# Ethernet-PoE-Sheet.net
KiCad netlist of a schematic drawn in Altium Designer
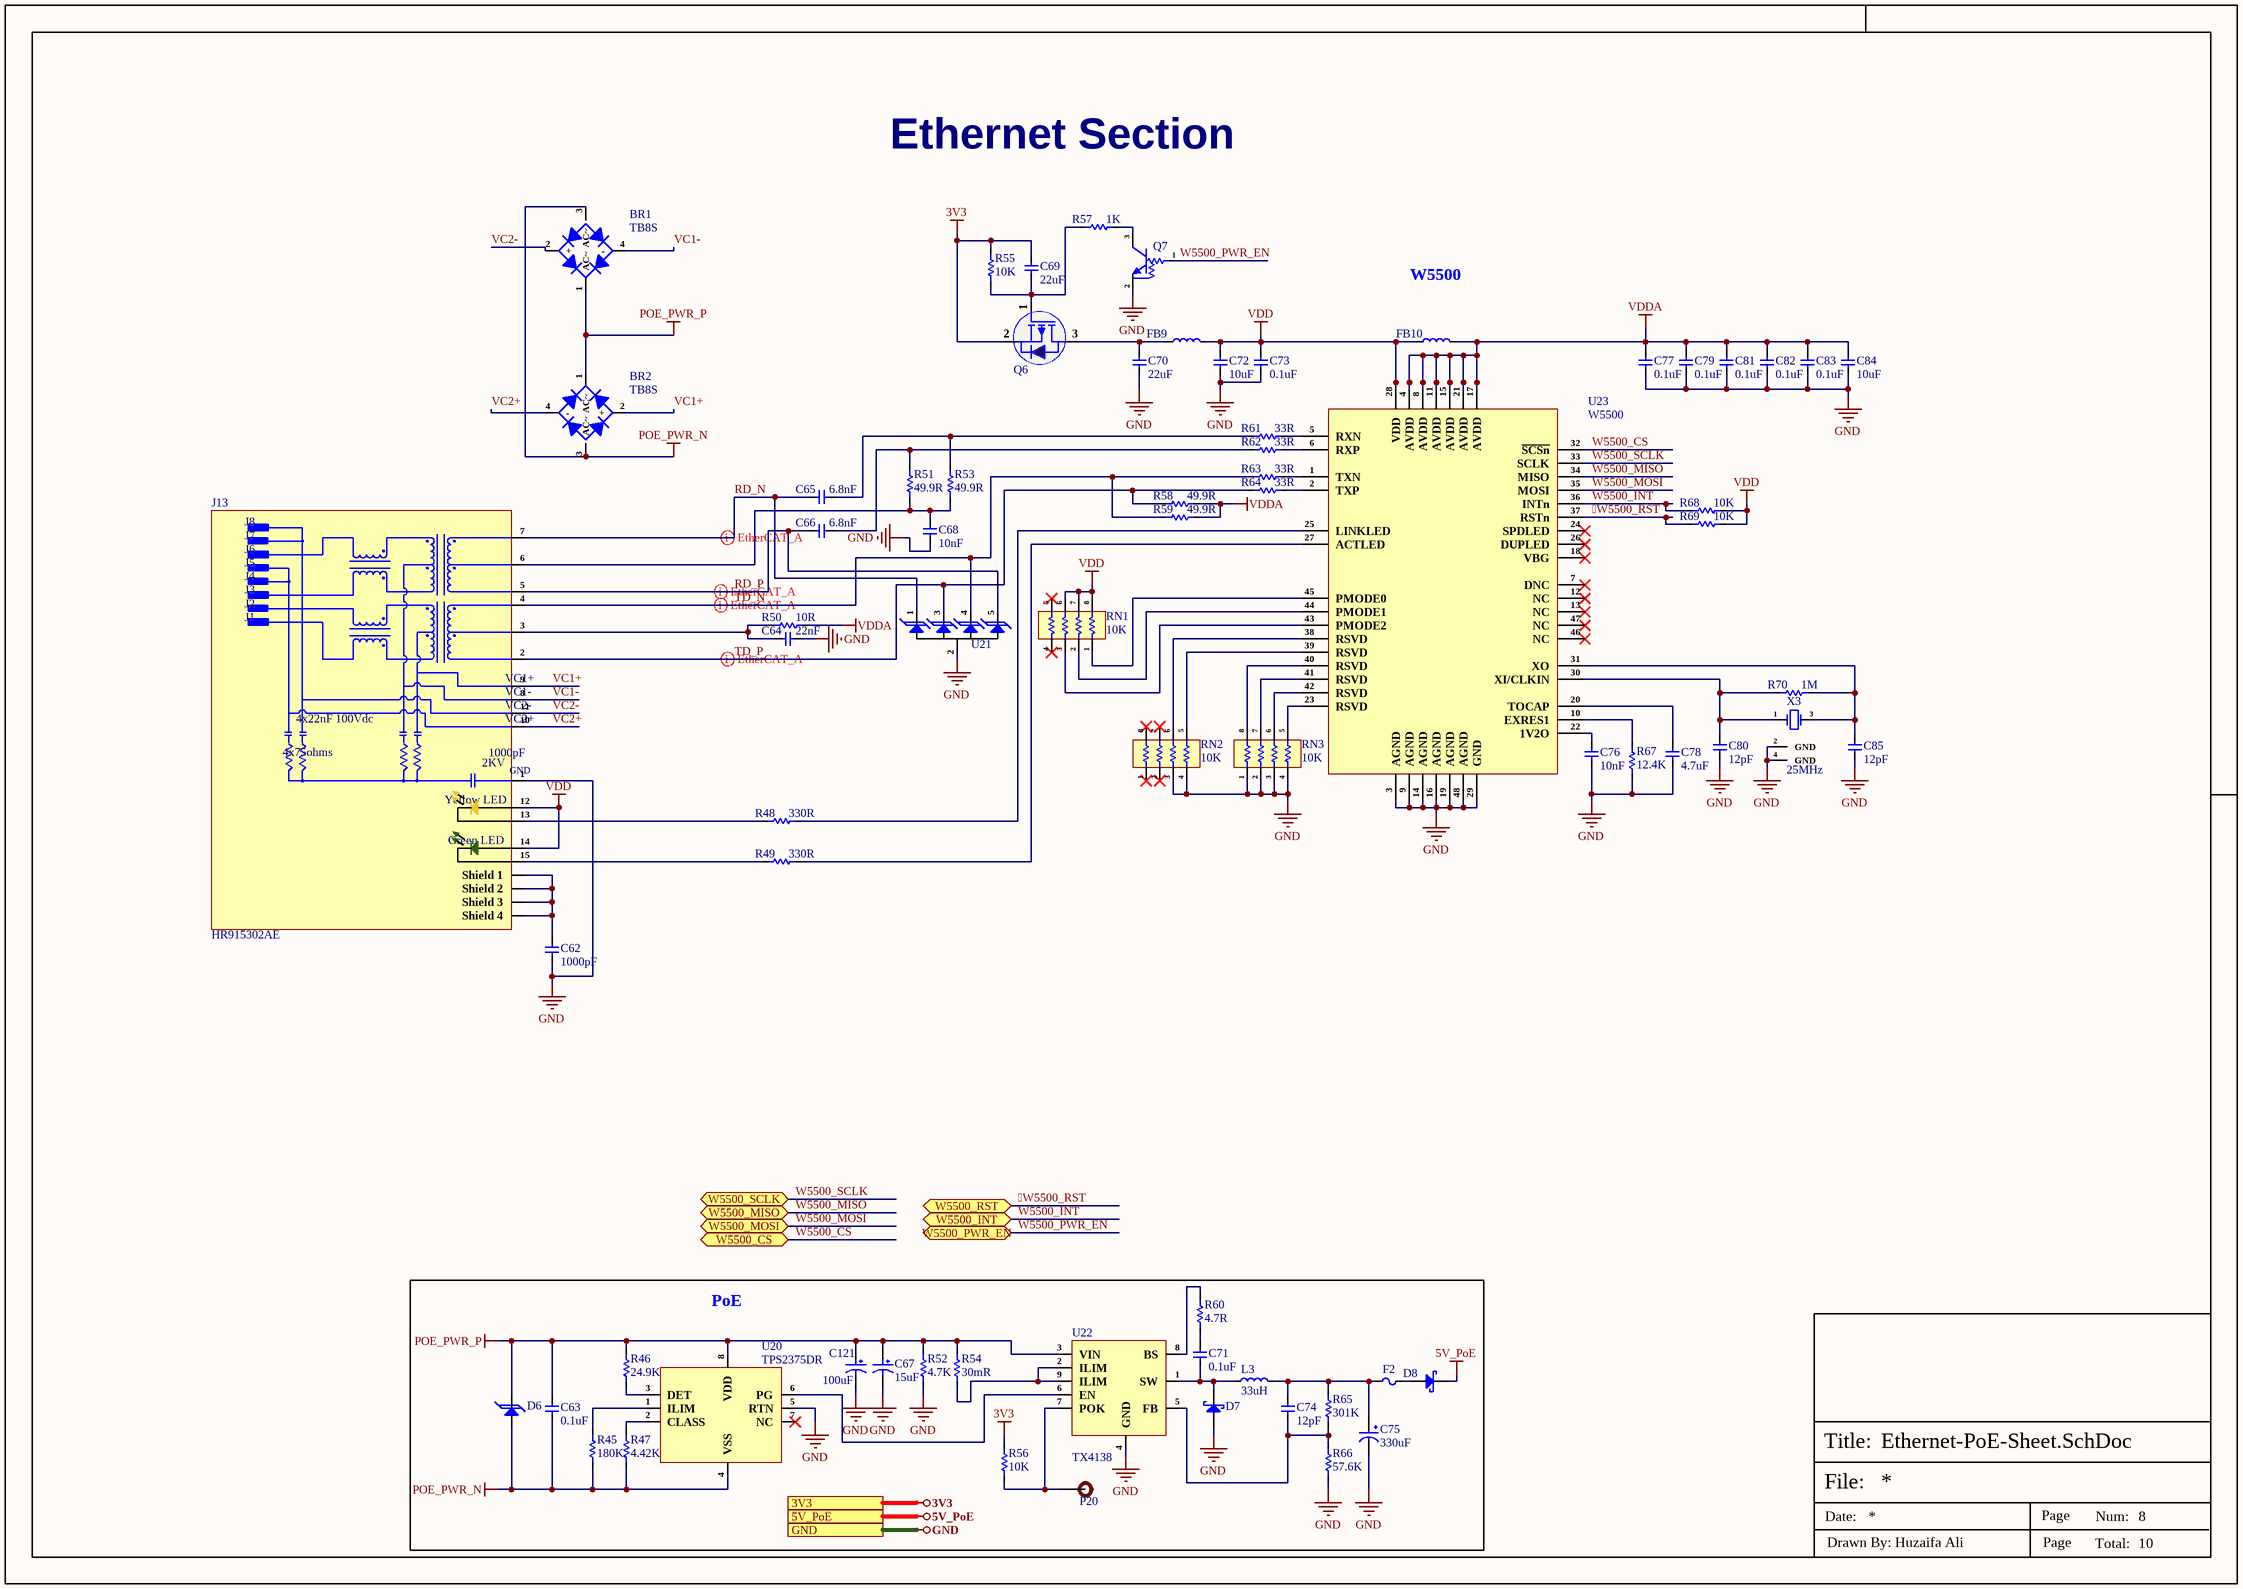
[diagram p0: Ethernet-PoE-Sheet.SchDoc]

(export (version "E")
  (design (tool "Eeschema 10.0.6"))
  (components
    (comp (ref "BR1")
      (value "TB8S")
      (footprint "TB8S")
      (description "30A 950mV@1A 1A 800V TBS Bridge Rectifiers ROHS")
      (fields (field (name "MANUFACTURER") "MDD") (field (name "LCSC PART NUMBER") "C65030"))
      (libsource (lib "eSpark Libraries") (part "TB8S"))
    )
    (comp (ref "BR2")
      (value "TB8S")
      (footprint "TB8S")
      (description "30A 950mV@1A 1A 800V TBS Bridge Rectifiers ROHS")
      (fields (field (name "MANUFACTURER") "MDD") (field (name "LCSC PART NUMBER") "C65030"))
      (libsource (lib "eSpark Libraries") (part "TB8S"))
    )
    (comp (ref "C62")
      (value "1000pF")
      (footprint "Cap-1206")
      (description "CAP CER 1000PF 2KV X7R 1206")
      (fields
        (field (name "MANUFACTURER") "Yageo")
        (field (name "MANUFACTURER PART NUMBER") "CC1206KKX7RDBB102")
      )
      (libsource (lib "eSpark_centralized_Library(2022)") (part "CC1206KKX7RDBB102"))
    )
    (comp (ref "C63")
      (value "0.1uF")
      (footprint "Cap-0603")
      (description "CAP CER 0.1UF 100V X7R 0603")
      (fields
        (field (name "MANUFACTURER") "Yageo")
        (field (name "MANUFACTURER PART NUMBER") "CC0603KRX7R0BB104")
      )
      (libsource (lib "eSpark_centralized_Library(2022)") (part "CC0603KRX7R0BB104"))
    )
    (comp (ref "C64")
      (value "22nF")
      (footprint "Cap-0603")
      (description "CAP CER 0.022UF 50V X7R 0603")
      (fields
        (field (name "MANUFACTURER") "Yageo")
        (field (name "MANUFACTURER PART NUMBER") "CC0603KRX7R9BB223")
      )
      (libsource (lib "eSpark_centralized_Library(2022)") (part "CC0603KRX7R9BB223"))
    )
    (comp (ref "C65")
      (value "6.8nF")
      (footprint "Cap-0603")
      (description "50V 6.8nF X7R ±10% 0603")
      (fields (field (name "MANUFACTURER") "FH") (field (name "MANUFACTURER PART NUMBER") "0603B682K500NT"))
      (libsource (lib "eSpark_centralized_Library(2022)") (part "0603B682K500NT"))
    )
    (comp (ref "C66")
      (value "6.8nF")
      (footprint "Cap-0603")
      (description "50V 6.8nF X7R ±10% 0603")
      (fields (field (name "MANUFACTURER") "FH") (field (name "MANUFACTURER PART NUMBER") "0603B682K500NT"))
      (libsource (lib "eSpark_centralized_Library(2022)") (part "0603B682K500NT"))
    )
    (comp (ref "C67")
      (value "15uF")
      (footprint "VMMC0571J150MV")
      (description "15uF 63V ±20% SMD,D6.3xL5.7mm Aluminum Electrolytic Capacitors - SMD ROHS")
      (fields (field (name "MANUFACTURER") "Ymin") (field (name "MANUFACTURER PART NUMBER") "VMMC0571J150MV"))
      (libsource (lib "eSpark_centralized_Library(2022)") (part "VMMC0571J150MV"))
    )
    (comp (ref "C68")
      (value "10nF")
      (footprint "Cap-0603")
      (description "CAP CER 10000PF 50V C0G/NPO 0603")
      (fields
        (field (name "MANUFACTURER") "Yageo")
        (field (name "MANUFACTURER PART NUMBER") "CC0603JRNPO9BN103")
      )
      (libsource (lib "eSpark_centralized_Library(2022)") (part "CC0603JRNPO9BN103"))
    )
    (comp (ref "C69")
      (value "22uF")
      (footprint "Cap-0805")
      (description "CAP CER 22UF 25V X5R 0805")
      (fields
        (field (name "MANUFACTURER") "Yageo")
        (field (name "MANUFACTURER PART NUMBER") "CC0805MKX5R8BB226")
      )
      (libsource (lib "eSpark_centralized_Library(2022)") (part "CC0805MKX5R8BB226"))
    )
    (comp (ref "C70")
      (value "22uF")
      (footprint "Cap-0805")
      (description "CAP CER 22UF 25V X5R 0805")
      (fields
        (field (name "MANUFACTURER") "Yageo")
        (field (name "MANUFACTURER PART NUMBER") "CC0805MKX5R8BB226")
      )
      (libsource (lib "eSpark_centralized_Library(2022)") (part "CC0805MKX5R8BB226"))
    )
    (comp (ref "C71")
      (value "0.1uF")
      (footprint "Cap-0603")
      (description "CAP CER 0.1UF 100V X7R 0603")
      (fields
        (field (name "MANUFACTURER") "Yageo")
        (field (name "MANUFACTURER PART NUMBER") "CC0603KRX7R0BB104")
      )
      (libsource (lib "eSpark_centralized_Library(2022)") (part "CC0603KRX7R0BB104"))
    )
    (comp (ref "C72")
      (value "10uF")
      (footprint "Cap-0603")
      (description "CAP CER 10UF 16V X5R 0603")
      (fields
        (field (name "MANUFACTURER") "Yageo")
        (field (name "MANUFACTURER PART NUMBER") "CC0603KRX5R7BB106")
      )
      (libsource (lib "eSpark_centralized_Library(2022)") (part "CC0603KRX5R7BB106"))
    )
    (comp (ref "C73")
      (value "0.1uF")
      (footprint "Cap-0402")
      (description "CAP CER 0.1UF 50V X5R 0402")
      (fields
        (field (name "MANUFACTURER") "TDK")
        (field (name "MANUFACTURER PART NUMBER") "C1005X5R1H104K050BB")
      )
      (libsource (lib "eSpark_centralized_Library(2022)") (part "C1005X5R1H104K050BB"))
    )
    (comp (ref "C74")
      (value "12pF")
      (footprint "Cap-0603")
      (description "CAP CER 12PF 50V C0G/NPO 0603")
      (fields
        (field (name "MANUFACTURER") "Yageo")
        (field (name "MANUFACTURER PART NUMBER") "CC0603J*NPO9B*120")
      )
      (libsource (lib "eSpark_centralized_Library(2022)") (part "CC0603JRNPO9BN120"))
    )
    (comp (ref "C75")
      (value "330uF")
      (footprint "Case-E")
      (description "CAP TANT 330UF 20% 16V 2917")
      (fields
        (field (name "MANUFACTURER") "Kyocera AVX")
        (field (name "MANUFACTURER PART NUMBER") "TAJE337M016RNJ")
      )
      (libsource (lib "eSpark_centralized_Library(2022)") (part "TAJE337M016RNJ"))
    )
    (comp (ref "C76")
      (value "10nF")
      (footprint "Cap-0603")
      (description "CAP CER 10000PF 50V C0G/NPO 0603")
      (fields
        (field (name "MANUFACTURER") "Yageo")
        (field (name "MANUFACTURER PART NUMBER") "CC0603JRNPO9BN103")
      )
      (libsource (lib "eSpark_centralized_Library(2022)") (part "CC0603JRNPO9BN103"))
    )
    (comp (ref "C77")
      (value "0.1uF")
      (footprint "Cap-0402")
      (description "CAP CER 0.1UF 50V X5R 0402")
      (fields
        (field (name "MANUFACTURER") "TDK")
        (field (name "MANUFACTURER PART NUMBER") "C1005X5R1H104K050BB")
      )
      (libsource (lib "eSpark_centralized_Library(2022)") (part "C1005X5R1H104K050BB"))
    )
    (comp (ref "C78")
      (value "4.7uF")
      (footprint "Cap-0603")
      (description "CAP CER 4.7UF 10V X5R 0603")
      (fields
        (field (name "MANUFACTURER") "Yageo")
        (field (name "MANUFACTURER PART NUMBER") "CC0603KRX5R6BB475")
      )
      (libsource (lib "eSpark_centralized_Library(2022)") (part "CC0603KRX5R6BB475"))
    )
    (comp (ref "C79")
      (value "0.1uF")
      (footprint "Cap-0402")
      (description "CAP CER 0.1UF 50V X5R 0402")
      (fields
        (field (name "MANUFACTURER") "TDK")
        (field (name "MANUFACTURER PART NUMBER") "C1005X5R1H104K050BB")
      )
      (libsource (lib "eSpark_centralized_Library(2022)") (part "C1005X5R1H104K050BB"))
    )
    (comp (ref "C80")
      (value "12pF")
      (footprint "Cap-0603")
      (description "CAP CER 12PF 50V C0G/NPO 0603")
      (fields
        (field (name "MANUFACTURER") "Yageo")
        (field (name "MANUFACTURER PART NUMBER") "CC0603J*NPO9B*120")
      )
      (libsource (lib "eSpark_centralized_Library(2022)") (part "CC0603JRNPO9BN120"))
    )
    (comp (ref "C81")
      (value "0.1uF")
      (footprint "Cap-0402")
      (description "CAP CER 0.1UF 50V X5R 0402")
      (fields
        (field (name "MANUFACTURER") "TDK")
        (field (name "MANUFACTURER PART NUMBER") "C1005X5R1H104K050BB")
      )
      (libsource (lib "eSpark_centralized_Library(2022)") (part "C1005X5R1H104K050BB"))
    )
    (comp (ref "C82")
      (value "0.1uF")
      (footprint "Cap-0402")
      (description "CAP CER 0.1UF 50V X5R 0402")
      (fields
        (field (name "MANUFACTURER") "TDK")
        (field (name "MANUFACTURER PART NUMBER") "C1005X5R1H104K050BB")
      )
      (libsource (lib "eSpark_centralized_Library(2022)") (part "C1005X5R1H104K050BB"))
    )
    (comp (ref "C83")
      (value "0.1uF")
      (footprint "Cap-0402")
      (description "CAP CER 0.1UF 50V X5R 0402")
      (fields
        (field (name "MANUFACTURER") "TDK")
        (field (name "MANUFACTURER PART NUMBER") "C1005X5R1H104K050BB")
      )
      (libsource (lib "eSpark_centralized_Library(2022)") (part "C1005X5R1H104K050BB"))
    )
    (comp (ref "C84")
      (value "10uF")
      (footprint "Cap-0603")
      (description "CAP CER 10UF 16V X5R 0603")
      (fields
        (field (name "MANUFACTURER") "Yageo")
        (field (name "MANUFACTURER PART NUMBER") "CC0603KRX5R7BB106")
      )
      (libsource (lib "eSpark_centralized_Library(2022)") (part "CC0603KRX5R7BB106"))
    )
    (comp (ref "C85")
      (value "12pF")
      (footprint "Cap-0603")
      (description "CAP CER 12PF 50V C0G/NPO 0603")
      (fields
        (field (name "MANUFACTURER") "Yageo")
        (field (name "MANUFACTURER PART NUMBER") "CC0603J*NPO9B*120")
      )
      (libsource (lib "eSpark_centralized_Library(2022)") (part "CC0603JRNPO9BN120"))
    )
    (comp (ref "C121")
      (value "100uF")
      (footprint "VKMD1451K101MV")
      (description "100uF 80V 735mA@100kHz ±20% SMD,D8xL14.5mm Aluminum Electrolytic Capacitors - SMD ROHS")
      (fields (field (name "MANUFACTURER") "Ymin") (field (name "MANUFACTURER PART NUMBER") "VKMD1451K101MV"))
      (libsource (lib "eSpark Libraries") (part "VKMD1451K101MV"))
    )
    (comp (ref "D6")
      (value "SMAJ58A")
      (footprint "SMA")
      (description "93.6V 64.4V 58V SMA(DO-214AC) TVS ROHS")
      (fields
        (field (name "MANUFACTURER") "Yangzhou Yangjie Elec Tech")
        (field (name "LCSC PART NUMBER") "C698958")
      )
      (libsource (lib "eSpark_centralized_Library(2022)") (part "SMAJ58A"))
    )
    (comp (ref "D7")
      (value "SS510B")
      (footprint "SMB_")
      (description "SCHOTTKY DIODE SMB 100V 5A")
      (fields (field (name "MANUFACTURER") "MDD") (field (name "LCSC PART NUMBER") "C3011128"))
      (libsource (lib "eSpark_centralized_Library(2022)") (part "SS510B"))
    )
    (comp (ref "D8")
      (value "PMEG4030ER")
      (footprint "SOD-123FL")
      (description "SOD-123FL Schottky Barrier Diodes (SBD) ROHS")
      (fields (field (name "MANUFACTURER") "Shikues") (field (name "LCSC PART NUMBER") "C5366303"))
      (libsource (lib "eSpark_centralized_Library(2022)") (part "PMEG4030ER"))
    )
    (comp (ref "F2")
      (value "BSMD0805L-200")
      (footprint "Fuse-0805")
      (description "6V 2A 50A 1W -40℃~+85℃ 4A 4mΩ 5s 45mΩ 0805 Resettable Fuses ROHS")
      (fields (field (name "MANUFACTURER") "BHFUSE") (field (name "LCSC PART NUMBER") "C2757931"))
      (libsource (lib "eSpark_centralized_Library(2022)") (part "BSMD0805L-200"))
    )
    (comp (ref "FB9")
      (value "CBM201209U601T")
      (footprint "Ind-0805")
      (description "100mΩ ±25% 600Ω@100MHz 0805 Ferrite Beads ROHS")
      (fields (field (name "MANUFACTURER") "FH") (field (name "LCSC PART NUMBER") "C139168"))
      (libsource (lib "eSpark_centralized_Library(2022)") (part "CBM201209U601T"))
    )
    (comp (ref "FB10")
      (value "CBM201209U601T")
      (footprint "Ind-0805")
      (description "100mΩ ±25% 600Ω@100MHz 0805 Ferrite Beads ROHS")
      (fields (field (name "MANUFACTURER") "FH") (field (name "LCSC PART NUMBER") "C139168"))
      (libsource (lib "eSpark_centralized_Library(2022)") (part "CBM201209U601T"))
    )
    (comp (ref "J13")
      (value "HR915302AE")
      (footprint "HR915302AE")
      (libsource (lib "eSpark Libraries") (part "HR915302AE"))
    )
    (comp (ref "L3")
      (value "33uH")
      (footprint "CYH127-33UH")
      (description "3A 33uH ±20% 64.8mΩ SMD,12.3x12.3mm Inductors (SMD) ROHS")
      (fields
        (field (name "MANUFACTURER") "SHOU HAN")
        (field (name "MANUFACTURER PART NUMBER") "CYH127-33UH")
      )
      (libsource (lib "eSpark_centralized_Library(2022)") (part "CYH127-33UH"))
    )
    (comp (ref "P20")
      (value "TEST POINT")
      (footprint "Test-point")
      (description "Test Point ON")
      (libsource (lib "eSpark_centralized_Library(2022)") (part "TEST POINT"))
    )
    (comp (ref "Q6")
      (value "WPM2015-3/TR")
      (footprint "Sot-23")
      (description "20V 2.2A 800mW 110mΩ@4.5V,2.7A 810mV@250uA P Channel SOT-23 MOSFETs ROHS")
      (fields (field (name "MANUFACTURER") "WILLSEMI") (field (name "LCSC PART NUMBER") "C213159"))
      (libsource (lib "eSpark_centralized_Library(2022)") (part "WPM2015-3/TR"))
    )
    (comp (ref "Q7")
      (value "LMUN2211LT1G")
      (footprint "SOT-23")
      (description "NPN 246mW 100mA 50V SOT-23 Digital Transistors ROHS")
      (fields (field (name "MANUFACTURER") "LRC") (field (name "LCSC PART NUMBER") "C12775"))
      (libsource (lib "eSpark_centralized_Library(2022)") (part "LMUN2211LT1G"))
    )
    (comp (ref "R45")
      (value "180K")
      (footprint "Res-0603")
      (description "RES 180K OHM 1% 1/10W 0603")
      (fields
        (field (name "MANUFACTURER") "Yageo")
        (field (name "MANUFACTURER PART NUMBER") "RC0603FR-07180KL")
      )
      (libsource (lib "eSpark_centralized_Library(2022)") (part "RC0603FR-07180KL"))
    )
    (comp (ref "R46")
      (value "24.9K")
      (footprint "Res-0603")
      (description "100mW Thick Film Resistors 75V ±100ppm/℃ ±1% 24.9kΩ 0603 Chip Resistor - Surface Mount ROHS")
      (fields
        (field (name "MANUFACTURER") "UNI-ROYAL(Uniroyal Elec)")
        (field (name "MANUFACTURER PART NUMBER") "0603WAF2492T5E")
      )
      (libsource (lib "eSpark Libraries") (part "0603WAF2492T5E"))
    )
    (comp (ref "R47")
      (value "4.42K")
      (footprint "Res-0603")
      (description "RES SMD 4.42K OHM 1% 1/10W 0603")
      (fields
        (field (name "MANUFACTURER") "Yageo")
        (field (name "MANUFACTURER PART NUMBER") "AC0603FR-074K42L")
      )
      (libsource (lib "eSpark_centralized_Library(2022)") (part "AC0603FR-074K42L"))
    )
    (comp (ref "R48")
      (value "330R")
      (footprint "Res-0603")
      (description "RES  SMD 330R 100 mW 0603")
      (fields
        (field (name "MANUFACTURER") "Yageo")
        (field (name "MANUFACTURER PART NUMBER") "RC0603JR-07330RL")
      )
      (libsource (lib "eSpark_centralized_Library(2022)") (part "RC0603JR-07330RL"))
    )
    (comp (ref "R49")
      (value "330R")
      (footprint "Res-0603")
      (description "RES  SMD 330R 100 mW 0603")
      (fields
        (field (name "MANUFACTURER") "Yageo")
        (field (name "MANUFACTURER PART NUMBER") "RC0603JR-07330RL")
      )
      (libsource (lib "eSpark_centralized_Library(2022)") (part "RC0603JR-07330RL"))
    )
    (comp (ref "R50")
      (value "10R")
      (footprint "Res-0603")
      (description "RES SMD 10 OHM 1% 1/10W 0603")
      (fields
        (field (name "MANUFACTURER") "Yageo")
        (field (name "MANUFACTURER PART NUMBER") "RC0603FR-0710RL")
      )
      (libsource (lib "eSpark_centralized_Library(2022)") (part "RC0603FR-0710RL"))
    )
    (comp (ref "R51")
      (value "49.9R")
      (footprint "Res-0603")
      (description "RES 49.9 OHM 1% 1/10W 0603")
      (fields
        (field (name "MANUFACTURER") "Yageo")
        (field (name "MANUFACTURER PART NUMBER") "RC0603FR-0749R9L")
      )
      (libsource (lib "eSpark_centralized_Library(2022)") (part "RC0603FR-0749R9L"))
    )
    (comp (ref "R52")
      (value "4.7K")
      (footprint "Res-0603")
      (description "RES SMD 4.7K OHM 1% 1/10W 0603")
      (fields
        (field (name "MANUFACTURER") "Yageo")
        (field (name "MANUFACTURER PART NUMBER") "RC0603FR-074K7L")
      )
      (libsource (lib "eSpark_centralized_Library(2022)") (part "RC0603FR-074K7L"))
    )
    (comp (ref "R53")
      (value "49.9R")
      (footprint "Res-0603")
      (description "RES 49.9 OHM 1% 1/10W 0603")
      (fields
        (field (name "MANUFACTURER") "Yageo")
        (field (name "MANUFACTURER PART NUMBER") "RC0603FR-0749R9L")
      )
      (libsource (lib "eSpark_centralized_Library(2022)") (part "RC0603FR-0749R9L"))
    )
    (comp (ref "R54")
      (value "30mR")
      (footprint "RES-0805")
      (description "RES 0.03 OHM 1% 1/2W 0805")
      (fields
        (field (name "MANUFACTURER") "Yageo")
        (field (name "MANUFACTURER PART NUMBER") "PE0805FRF470R03L")
      )
      (libsource (lib "eSpark_centralized_Library(2022)") (part "PE0805FRF470R03L"))
    )
    (comp (ref "R55")
      (value "10K")
      (footprint "Res-0402")
      (description "RES 10K OHM 1% 1/16W 0402")
      (fields
        (field (name "MANUFACTURER") "Yageo")
        (field (name "MANUFACTURER PART NUMBER") "RC0402FR-0710KL")
      )
      (libsource (lib "eSpark_centralized_Library(2022)") (part "RC0402FR-0710KL"))
    )
    (comp (ref "R56")
      (value "10K")
      (footprint "Res-0402")
      (description "RES 10K OHM 1% 1/16W 0402")
      (fields
        (field (name "MANUFACTURER") "Yageo")
        (field (name "MANUFACTURER PART NUMBER") "RC0402FR-0710KL")
      )
      (libsource (lib "eSpark_centralized_Library(2022)") (part "RC0402FR-0710KL"))
    )
    (comp (ref "R57")
      (value "1K")
      (footprint "Res-0603")
      (description "RES SMD 1K OHM 1% 1/10W 0603")
      (fields
        (field (name "MANUFACTURER") "Yageo")
        (field (name "MANUFACTURER PART NUMBER") "RC0603FR-071KL")
      )
      (libsource (lib "eSpark_centralized_Library(2022)") (part "RC0603FR-071KL"))
    )
    (comp (ref "R58")
      (value "49.9R")
      (footprint "Res-0603")
      (description "RES 49.9 OHM 1% 1/10W 0603")
      (fields
        (field (name "MANUFACTURER") "Yageo")
        (field (name "MANUFACTURER PART NUMBER") "RC0603FR-0749R9L")
      )
      (libsource (lib "eSpark_centralized_Library(2022)") (part "RC0603FR-0749R9L"))
    )
    (comp (ref "R59")
      (value "49.9R")
      (footprint "Res-0603")
      (description "RES 49.9 OHM 1% 1/10W 0603")
      (fields
        (field (name "MANUFACTURER") "Yageo")
        (field (name "MANUFACTURER PART NUMBER") "RC0603FR-0749R9L")
      )
      (libsource (lib "eSpark_centralized_Library(2022)") (part "RC0603FR-0749R9L"))
    )
    (comp (ref "R60")
      (value "4.7R")
      (footprint "Res-0603")
      (description "RES 4.7 OHM 1% 1/10W 0603")
      (fields
        (field (name "MANUFACTURER") "Yageo")
        (field (name "MANUFACTURER PART NUMBER") "RC0603FR-074R7L")
      )
      (libsource (lib "eSpark_centralized_Library(2022)") (part "RC0603FR-074R7L"))
    )
    (comp (ref "R61")
      (value "33R")
      (footprint "Res-0603")
      (description "RES SMD 0603 33 Ohm 1% 1/10W")
      (fields
        (field (name "MANUFACTURER") "Yageo")
        (field (name "MANUFACTURER PART NUMBER") "RC0603FR-0733RL")
      )
      (libsource (lib "eSpark_centralized_Library(2022)") (part "RC0603FR-0733RL"))
    )
    (comp (ref "R62")
      (value "33R")
      (footprint "Res-0603")
      (description "RES SMD 0603 33 Ohm 1% 1/10W")
      (fields
        (field (name "MANUFACTURER") "Yageo")
        (field (name "MANUFACTURER PART NUMBER") "RC0603FR-0733RL")
      )
      (libsource (lib "eSpark_centralized_Library(2022)") (part "RC0603FR-0733RL"))
    )
    (comp (ref "R63")
      (value "33R")
      (footprint "Res-0603")
      (description "RES SMD 0603 33 Ohm 1% 1/10W")
      (fields
        (field (name "MANUFACTURER") "Yageo")
        (field (name "MANUFACTURER PART NUMBER") "RC0603FR-0733RL")
      )
      (libsource (lib "eSpark_centralized_Library(2022)") (part "RC0603FR-0733RL"))
    )
    (comp (ref "R64")
      (value "33R")
      (footprint "Res-0603")
      (description "RES SMD 0603 33 Ohm 1% 1/10W")
      (fields
        (field (name "MANUFACTURER") "Yageo")
        (field (name "MANUFACTURER PART NUMBER") "RC0603FR-0733RL")
      )
      (libsource (lib "eSpark_centralized_Library(2022)") (part "RC0603FR-0733RL"))
    )
    (comp (ref "R65")
      (value "301K")
      (footprint "Res-0603")
      (description "100mW Thin Film Resistor ±25ppm/℃ ±0.1% 301kΩ 0603 Chip Resistor - Surface Mount ROHS")
      (fields
        (field (name "MANUFACTURER") "YAGEO")
        (field (name "MANUFACTURER PART NUMBER") "RT0603BRD07301KL")
      )
      (libsource (lib "eSpark Libraries") (part "RT0603BRD07301KL"))
    )
    (comp (ref "R66")
      (value "57.6K")
      (footprint "Res-0603")
      (description "RES SMD 57.6KOHM 0.1% 1/10W 0603")
      (fields
        (field (name "MANUFACTURER") "YAGEO")
        (field (name "MANUFACTURER PART NUMBER") "RT0603BRE0757K6L")
      )
      (libsource (lib "eSpark_centralized_Library(2022)") (part "RT0603BRE0757K6L"))
    )
    (comp (ref "R67")
      (value "12.4K")
      (footprint "Res-0603")
      (description "RES SMD 12.4K OHM 1% 1/10W 0603")
      (fields
        (field (name "MANUFACTURER") "Yageo")
        (field (name "MANUFACTURER PART NUMBER") "RC0603FR-0712K4L")
      )
      (libsource (lib "eSpark_centralized_Library(2022)") (part "RC0603FR-0712K4L"))
    )
    (comp (ref "R68")
      (value "10K")
      (footprint "Res-0402")
      (description "RES 10K OHM 1% 1/16W 0402")
      (fields
        (field (name "MANUFACTURER") "Yageo")
        (field (name "MANUFACTURER PART NUMBER") "RC0402FR-0710KL")
      )
      (libsource (lib "eSpark_centralized_Library(2022)") (part "RC0402FR-0710KL"))
    )
    (comp (ref "R69")
      (value "10K")
      (footprint "Res-0402")
      (description "RES 10K OHM 1% 1/16W 0402")
      (fields
        (field (name "MANUFACTURER") "Yageo")
        (field (name "MANUFACTURER PART NUMBER") "RC0402FR-0710KL")
      )
      (libsource (lib "eSpark_centralized_Library(2022)") (part "RC0402FR-0710KL"))
    )
    (comp (ref "R70")
      (value "1M")
      (footprint "Res-0603")
      (description "RES SMD 1M OHM 1% 1/10W 0603")
      (fields
        (field (name "MANUFACTURER") "Yageo")
        (field (name "MANUFACTURER PART NUMBER") "RC0603FR-071ML")
      )
      (libsource (lib "eSpark_centralized_Library(2022)") (part "RC0603FR-071ML"))
    )
    (comp (ref "RN1")
      (value "10K")
      (footprint "YC164-FR-0710KL")
      (description "RES ARRAY 4 RES 10K OHM 1206")
      (fields
        (field (name "MANUFACTURER") "Yageo")
        (field (name "MANUFACTURER PART NUMBER") "YC164-FR-0710KL")
      )
      (libsource (lib "eSpark_centralized_Library(2022)") (part "YC164-FR-0710KL"))
    )
    (comp (ref "RN2")
      (value "10K")
      (footprint "YC164-FR-0710KL")
      (description "RES ARRAY 4 RES 10K OHM 1206")
      (fields
        (field (name "MANUFACTURER") "Yageo")
        (field (name "MANUFACTURER PART NUMBER") "YC164-FR-0710KL")
      )
      (libsource (lib "") (part "YC164-FR-0710KL_1"))
    )
    (comp (ref "RN3")
      (value "10K")
      (footprint "YC164-FR-0710KL")
      (description "RES ARRAY 4 RES 10K OHM 1206")
      (fields
        (field (name "MANUFACTURER") "Yageo")
        (field (name "MANUFACTURER PART NUMBER") "YC164-FR-0710KL")
      )
      (libsource (lib "") (part "YC164-FR-0710KL_1"))
    )
    (comp (ref "U20")
      (value "TPS2375DR")
      (footprint "SOIC-8")
      (description "IC POE CNTRL 1 CHANNEL 8SOIC")
      (fields (field (name "MANUFACTURER") "Texas Instruments") (field (name "LCSC PART NUMBER") "C2867397"))
      (libsource (lib "eSpark_centralized_Library(2022)") (part "TPS2375DR"))
    )
    (comp (ref "U21")
      (value "SP0504BAHTG")
      (footprint "SOT-23-5")
      (description "TVS DIODE 5.5VWM 8.5VC SOT23-5")
      (fields (field (name "MANUFACTURER") "Littelfuse") (field (name "LCSC PART NUMBER") "C10675"))
      (libsource (lib "eSpark_centralized_Library(2022)") (part "SP0504BAHTG"))
    )
    (comp (ref "U22")
      (value "TX4138")
      (footprint "8-SOIC-EP")
      (description "Step-down type SOIC-8-EP DC-DC Converters ROHS")
      (fields (field (name "MANUFACTURER") "XDS") (field (name "LCSC PART NUMBER") "C329267"))
      (libsource (lib "eSpark_centralized_Library(2022)") (part "TX4138"))
    )
    (comp (ref "U23")
      (value "W5500")
      (footprint "48-LQFP (7x7)_")
      (description "SPI LQFP-48(7x7) Ethernet ICs ROHS")
      (fields (field (name "MANUFACTURER") "WIZNET") (field (name "LCSC PART NUMBER") "C32843"))
      (libsource (lib "eSpark_centralized_Library(2022)") (part "W5500"))
    )
    (comp (ref "X3")
      (value "25MHz")
      (footprint "Q22FA12800090")
      (description "CRYSTAL 25.0000MHZ 12PF SMD")
      (fields
        (field (name "MANUFACTURER") "Seiko Epson")
        (field (name "MANUFACTURER PART NUMBER") "Q22FA12800090")
      )
      (libsource (lib "eSpark_centralized_Library(2022)") (part "Q22FA12800090"))
    )
  )
  (nets
    (net (code "1") (name "/W5500_RST") (class "Default")
      (node (ref "R69") (pin "2") (pinfunction "2_2") (pintype "passive"))
      (node (ref "U23") (pin "37") (pinfunction "RSTn_37") (pintype "passive"))
    )
    (net (code "2") (name "/RD_N") (class "Default")
      (node (ref "C65") (pin "1") (pinfunction "1_1") (pintype "passive"))
      (node (ref "J13") (pin "7") (pinfunction "P7_7") (pintype "passive"))
      (node (ref "U21") (pin "1") (pinfunction "K_1") (pintype "passive"))
    )
    (net (code "3") (name "/RD_P") (class "Default")
      (node (ref "C66") (pin "1") (pinfunction "1_1") (pintype "passive"))
      (node (ref "J13") (pin "5") (pinfunction "P5_5") (pintype "passive"))
      (node (ref "U21") (pin "5") (pinfunction "K_5") (pintype "passive"))
    )
    (net (code "4") (name "/TD_N") (class "Default")
      (node (ref "J13") (pin "4") (pinfunction "P4_4") (pintype "passive"))
      (node (ref "R59") (pin "1") (pinfunction "1_1") (pintype "passive"))
      (node (ref "R63") (pin "1") (pinfunction "1_1") (pintype "passive"))
      (node (ref "U21") (pin "4") (pinfunction "K_4") (pintype "passive"))
    )
    (net (code "5") (name "/TD_P") (class "Default")
      (node (ref "J13") (pin "2") (pinfunction "P2_2") (pintype "passive"))
      (node (ref "R58") (pin "1") (pinfunction "1_1") (pintype "passive"))
      (node (ref "R64") (pin "1") (pinfunction "1_1") (pintype "passive"))
      (node (ref "U21") (pin "3") (pinfunction "K_3") (pintype "passive"))
    )
    (net (code "6") (name "/VC1+") (class "Default")
      (node (ref "BR2") (pin "2") (pinfunction "+_2") (pintype "passive"))
      (node (ref "J13") (pin "9") (pinfunction "VC1+_9") (pintype "passive"))
    )
    (net (code "7") (name "/VC1-") (class "Default")
      (node (ref "BR1") (pin "4") (pinfunction "-_4") (pintype "passive"))
      (node (ref "J13") (pin "8") (pinfunction "VC1-_8") (pintype "passive"))
    )
    (net (code "8") (name "/VC2+") (class "Default")
      (node (ref "BR2") (pin "4") (pinfunction "-_4") (pintype "passive"))
      (node (ref "J13") (pin "10") (pinfunction "VC2+_10") (pintype "passive"))
    )
    (net (code "9") (name "/VC2-") (class "Default")
      (node (ref "BR1") (pin "2") (pinfunction "+_2") (pintype "passive"))
      (node (ref "J13") (pin "11") (pinfunction "VC2-_11") (pintype "passive"))
    )
    (net (code "10") (name "/W5500_CS") (class "Default")
      (node (ref "U23") (pin "32") (pinfunction "~{SCSn}_32") (pintype "passive"))
    )
    (net (code "11") (name "/W5500_INT") (class "Default")
      (node (ref "R68") (pin "2") (pinfunction "2_2") (pintype "passive"))
      (node (ref "U23") (pin "36") (pinfunction "INTn_36") (pintype "passive"))
    )
    (net (code "12") (name "/W5500_MISO") (class "Default")
      (node (ref "U23") (pin "34") (pinfunction "MISO_34") (pintype "passive"))
    )
    (net (code "13") (name "/W5500_MOSI") (class "Default")
      (node (ref "U23") (pin "35") (pinfunction "MOSI_35") (pintype "passive"))
    )
    (net (code "14") (name "/W5500_PWR_EN") (class "Default")
      (node (ref "Q7") (pin "1") (pinfunction "B_1") (pintype "passive"))
    )
    (net (code "15") (name "/W5500_SCLK") (class "Default")
      (node (ref "U23") (pin "33") (pinfunction "SCLK_33") (pintype "passive"))
    )
    (net (code "16") (name "3V3") (class "Default")
      (node (ref "C69") (pin "2") (pinfunction "2_2") (pintype "passive"))
      (node (ref "Q6") (pin "2") (pinfunction "S_2") (pintype "passive"))
      (node (ref "R55") (pin "1") (pinfunction "1_1") (pintype "passive"))
      (node (ref "R56") (pin "2") (pinfunction "2_2") (pintype "passive"))
    )
    (net (code "17") (name "5V_PoE") (class "Default")
      (node (ref "D8") (pin "1") (pinfunction "K_1") (pintype "passive"))
    )
    (net (code "18") (name "GND") (class "Default")
      (node (ref "C121") (pin "2") (pintype "passive"))
      (node (ref "C62") (pin "1") (pinfunction "1_1") (pintype "passive"))
      (node (ref "C64") (pin "2") (pinfunction "2_2") (pintype "passive"))
      (node (ref "C67") (pin "2") (pintype "passive"))
      (node (ref "C68") (pin "1") (pinfunction "1_1") (pintype "passive"))
      (node (ref "C70") (pin "1") (pinfunction "1_1") (pintype "passive"))
      (node (ref "C72") (pin "1") (pinfunction "1_1") (pintype "passive"))
      (node (ref "C73") (pin "1") (pinfunction "1_1") (pintype "passive"))
      (node (ref "C75") (pin "2") (pinfunction "2_2") (pintype "passive"))
      (node (ref "C76") (pin "1") (pinfunction "1_1") (pintype "passive"))
      (node (ref "C77") (pin "1") (pinfunction "1_1") (pintype "passive"))
      (node (ref "C78") (pin "1") (pinfunction "1_1") (pintype "passive"))
      (node (ref "C79") (pin "1") (pinfunction "1_1") (pintype "passive"))
      (node (ref "C80") (pin "1") (pinfunction "1_1") (pintype "passive"))
      (node (ref "C81") (pin "1") (pinfunction "1_1") (pintype "passive"))
      (node (ref "C82") (pin "1") (pinfunction "1_1") (pintype "passive"))
      (node (ref "C83") (pin "1") (pinfunction "1_1") (pintype "passive"))
      (node (ref "C84") (pin "1") (pinfunction "1_1") (pintype "passive"))
      (node (ref "C85") (pin "1") (pinfunction "1_1") (pintype "passive"))
      (node (ref "D7") (pin "1") (pinfunction "A_1") (pintype "passive"))
      (node (ref "J13") (pin "1") (pinfunction "P1_1") (pintype "power_in"))
      (node (ref "Q7") (pin "2") (pinfunction "E_2") (pintype "passive"))
      (node (ref "R52") (pin "1") (pinfunction "1_1") (pintype "passive"))
      (node (ref "R66") (pin "1") (pinfunction "1_1") (pintype "passive"))
      (node (ref "R67") (pin "1") (pinfunction "1_1") (pintype "passive"))
      (node (ref "RN2") (pin "3") (pintype "passive"))
      (node (ref "RN2") (pin "4") (pintype "passive"))
      (node (ref "RN3") (pin "1") (pintype "passive"))
      (node (ref "RN3") (pin "2") (pintype "passive"))
      (node (ref "RN3") (pin "3") (pintype "passive"))
      (node (ref "RN3") (pin "4") (pintype "passive"))
      (node (ref "U20") (pin "5") (pinfunction "RTN_5") (pintype "passive"))
      (node (ref "U21") (pin "2") (pinfunction "A_2") (pintype "passive"))
      (node (ref "U22") (pin "4") (pinfunction "GND_4") (pintype "passive"))
      (node (ref "U23") (pin "14") (pinfunction "AGND_14") (pintype "passive"))
      (node (ref "U23") (pin "16") (pinfunction "AGND_16") (pintype "passive"))
      (node (ref "U23") (pin "19") (pinfunction "AGND_19") (pintype "passive"))
      (node (ref "U23") (pin "29") (pinfunction "GND_29") (pintype "passive"))
      (node (ref "U23") (pin "3") (pinfunction "AGND_3") (pintype "passive"))
      (node (ref "U23") (pin "48") (pinfunction "AGND_48") (pintype "passive"))
      (node (ref "U23") (pin "9") (pinfunction "AGND_9") (pintype "passive"))
      (node (ref "X3") (pin "2") (pinfunction "GND_2") (pintype "passive"))
      (node (ref "X3") (pin "4") (pinfunction "GND_4") (pintype "passive"))
    )
    (net (code "19") (name "Net-(C65-Pad2)") (class "Default")
      (node (ref "C65") (pin "2") (pinfunction "2_2") (pintype "passive"))
      (node (ref "R53") (pin "2") (pinfunction "2_2") (pintype "passive"))
      (node (ref "R61") (pin "1") (pinfunction "1_1") (pintype "passive"))
    )
    (net (code "20") (name "Net-(C66-Pad2)") (class "Default")
      (node (ref "C66") (pin "2") (pinfunction "2_2") (pintype "passive"))
      (node (ref "R51") (pin "2") (pinfunction "2_2") (pintype "passive"))
      (node (ref "R62") (pin "1") (pinfunction "1_1") (pintype "passive"))
    )
    (net (code "21") (name "Net-(C71-Pad2)") (class "Default")
      (node (ref "C71") (pin "2") (pinfunction "2_2") (pintype "passive"))
      (node (ref "R60") (pin "1") (pinfunction "1_1") (pintype "passive"))
    )
    (net (code "22") (name "Net-(C74-Pad2)") (class "Default")
      (node (ref "C74") (pin "2") (pinfunction "2_2") (pintype "passive"))
      (node (ref "C75") (pin "1") (pinfunction "1_1") (pintype "passive"))
      (node (ref "F2") (pin "1") (pinfunction "1_1") (pintype "passive"))
      (node (ref "L3") (pin "2") (pinfunction "2_2") (pintype "passive"))
      (node (ref "R65") (pin "2") (pinfunction "2_2") (pintype "passive"))
    )
    (net (code "23") (name "Net-(D7-K)") (class "Default")
      (node (ref "C71") (pin "1") (pinfunction "1_1") (pintype "passive"))
      (node (ref "D7") (pin "2") (pinfunction "K_2") (pintype "passive"))
      (node (ref "L3") (pin "1") (pinfunction "1_1") (pintype "passive"))
      (node (ref "U22") (pin "1") (pinfunction "SW_1") (pintype "passive"))
    )
    (net (code "24") (name "Net-(D8-A)") (class "Default")
      (node (ref "D8") (pin "2") (pinfunction "A_2") (pintype "passive"))
      (node (ref "F2") (pin "2") (pinfunction "2_2") (pintype "passive"))
    )
    (net (code "25") (name "Net-(J13-CATHODE-Pad13)") (class "Default")
      (node (ref "J13") (pin "13") (pinfunction "CATHODE_13") (pintype "passive"))
      (node (ref "R48") (pin "1") (pinfunction "1_1") (pintype "passive"))
    )
    (net (code "26") (name "Net-(J13-CATHODE-Pad15)") (class "Default")
      (node (ref "J13") (pin "15") (pinfunction "CATHODE_15") (pintype "passive"))
      (node (ref "R49") (pin "1") (pinfunction "1_1") (pintype "passive"))
    )
    (net (code "27") (name "Net-(J13-P3)") (class "Default")
      (node (ref "C64") (pin "1") (pinfunction "1_1") (pintype "passive"))
      (node (ref "J13") (pin "3") (pinfunction "P3_3") (pintype "passive"))
      (node (ref "R50") (pin "1") (pinfunction "1_1") (pintype "passive"))
    )
    (net (code "28") (name "Net-(J13-P6)") (class "Default")
      (node (ref "C68") (pin "2") (pinfunction "2_2") (pintype "passive"))
      (node (ref "J13") (pin "6") (pinfunction "P6_6") (pintype "passive"))
      (node (ref "R51") (pin "1") (pinfunction "1_1") (pintype "passive"))
      (node (ref "R53") (pin "1") (pinfunction "1_1") (pintype "passive"))
    )
    (net (code "29") (name "Net-(J13-Shield_1)") (class "Default")
      (node (ref "C62") (pin "2") (pinfunction "2_2") (pintype "passive"))
      (node (ref "J13") (pin "SH1") (pinfunction "Shield_1_SH1") (pintype "passive"))
      (node (ref "J13") (pin "SH2") (pinfunction "Shield_2_SH2") (pintype "passive"))
      (node (ref "J13") (pin "SH3") (pinfunction "Shield_3_SH3") (pintype "passive"))
      (node (ref "J13") (pin "SH4") (pinfunction "Shield_4_SH4") (pintype "passive"))
    )
    (net (code "30") (name "Net-(Q6-D)") (class "Default")
      (node (ref "C70") (pin "2") (pinfunction "2_2") (pintype "passive"))
      (node (ref "FB9") (pin "1") (pinfunction "1_1") (pintype "passive"))
      (node (ref "Q6") (pin "3") (pinfunction "D_3") (pintype "passive"))
    )
    (net (code "31") (name "Net-(Q6-G)") (class "Default")
      (node (ref "C69") (pin "1") (pinfunction "1_1") (pintype "passive"))
      (node (ref "Q6") (pin "1") (pinfunction "G_1") (pintype "passive"))
      (node (ref "R55") (pin "2") (pinfunction "2_2") (pintype "passive"))
      (node (ref "R57") (pin "1") (pinfunction "1_1") (pintype "passive"))
    )
    (net (code "32") (name "Net-(Q7-C)") (class "Default")
      (node (ref "Q7") (pin "3") (pinfunction "C_3") (pintype "passive"))
      (node (ref "R57") (pin "2") (pinfunction "2_2") (pintype "passive"))
    )
    (net (code "33") (name "Net-(R54-Pad1)") (class "Default")
      (node (ref "R54") (pin "1") (pinfunction "1_1") (pintype "passive"))
      (node (ref "U22") (pin "2") (pinfunction "ILIM_2") (pintype "passive"))
      (node (ref "U22") (pin "9") (pinfunction "ILIM_9") (pintype "passive"))
    )
    (net (code "34") (name "Net-(RN2-Pad5)") (class "Default")
      (node (ref "RN2") (pin "5") (pintype "passive"))
      (node (ref "U23") (pin "39") (pinfunction "RSVD_39") (pintype "passive"))
    )
    (net (code "35") (name "Net-(RN2-Pad6)") (class "Default")
      (node (ref "RN2") (pin "6") (pintype "passive"))
      (node (ref "U23") (pin "38") (pinfunction "RSVD_38") (pintype "passive"))
    )
    (net (code "36") (name "Net-(RN3-Pad5)") (class "Default")
      (node (ref "RN3") (pin "5") (pintype "passive"))
      (node (ref "U23") (pin "23") (pinfunction "RSVD_23") (pintype "passive"))
    )
    (net (code "37") (name "Net-(RN3-Pad6)") (class "Default")
      (node (ref "RN3") (pin "6") (pintype "passive"))
      (node (ref "U23") (pin "42") (pinfunction "RSVD_42") (pintype "passive"))
    )
    (net (code "38") (name "Net-(RN3-Pad7)") (class "Default")
      (node (ref "RN3") (pin "7") (pintype "passive"))
      (node (ref "U23") (pin "41") (pinfunction "RSVD_41") (pintype "passive"))
    )
    (net (code "39") (name "Net-(RN3-Pad8)") (class "Default")
      (node (ref "RN3") (pin "8") (pintype "passive"))
      (node (ref "U23") (pin "40") (pinfunction "RSVD_40") (pintype "passive"))
    )
    (net (code "40") (name "Net-(U20-CLASS)") (class "Default")
      (node (ref "R47") (pin "2") (pinfunction "2_2") (pintype "passive"))
      (node (ref "U20") (pin "2") (pinfunction "CLASS_2") (pintype "passive"))
    )
    (net (code "41") (name "Net-(U20-DET)") (class "Default")
      (node (ref "R46") (pin "1") (pinfunction "1_1") (pintype "passive"))
      (node (ref "U20") (pin "3") (pinfunction "DET_3") (pintype "passive"))
    )
    (net (code "42") (name "Net-(U20-ILIM)") (class "Default")
      (node (ref "R45") (pin "2") (pinfunction "2_2") (pintype "passive"))
      (node (ref "U20") (pin "1") (pinfunction "ILIM_1") (pintype "passive"))
    )
    (net (code "43") (name "Net-(U20-PG)") (class "Default")
      (node (ref "U20") (pin "6") (pinfunction "PG_6") (pintype "passive"))
      (node (ref "U22") (pin "6") (pinfunction "EN_6") (pintype "passive"))
    )
    (net (code "44") (name "Net-(U22-BS)") (class "Default")
      (node (ref "R60") (pin "2") (pinfunction "2_2") (pintype "passive"))
      (node (ref "U22") (pin "8") (pinfunction "BS_8") (pintype "passive"))
    )
    (net (code "45") (name "Net-(U22-FB)") (class "Default")
      (node (ref "C74") (pin "1") (pinfunction "1_1") (pintype "passive"))
      (node (ref "R65") (pin "1") (pinfunction "1_1") (pintype "passive"))
      (node (ref "R66") (pin "2") (pinfunction "2_2") (pintype "passive"))
      (node (ref "U22") (pin "5") (pinfunction "FB_5") (pintype "passive"))
    )
    (net (code "46") (name "Net-(U22-POK)") (class "Default")
      (node (ref "P20") (pin "1") (pinfunction "1_1") (pintype "passive"))
      (node (ref "R56") (pin "1") (pinfunction "1_1") (pintype "passive"))
      (node (ref "U22") (pin "7") (pinfunction "POK_7") (pintype "passive"))
    )
    (net (code "47") (name "Net-(U23-1V2O)") (class "Default")
      (node (ref "C76") (pin "2") (pinfunction "2_2") (pintype "passive"))
      (node (ref "U23") (pin "22") (pinfunction "1V2O_22") (pintype "passive"))
    )
    (net (code "48") (name "Net-(U23-ACTLED)") (class "Default")
      (node (ref "R49") (pin "2") (pinfunction "2_2") (pintype "passive"))
      (node (ref "U23") (pin "27") (pinfunction "ACTLED_27") (pintype "passive"))
    )
    (net (code "49") (name "Net-(U23-EXRES1)") (class "Default")
      (node (ref "R67") (pin "2") (pinfunction "2_2") (pintype "passive"))
      (node (ref "U23") (pin "10") (pinfunction "EXRES1_10") (pintype "passive"))
    )
    (net (code "50") (name "Net-(U23-LINKLED)") (class "Default")
      (node (ref "R48") (pin "2") (pinfunction "2_2") (pintype "passive"))
      (node (ref "U23") (pin "25") (pinfunction "LINKLED_25") (pintype "passive"))
    )
    (net (code "51") (name "Net-(U23-PMODE0)") (class "Default")
      (node (ref "RN1") (pin "1") (pintype "passive"))
      (node (ref "U23") (pin "45") (pinfunction "PMODE0_45") (pintype "passive"))
    )
    (net (code "52") (name "Net-(U23-PMODE1)") (class "Default")
      (node (ref "RN1") (pin "2") (pintype "passive"))
      (node (ref "U23") (pin "44") (pinfunction "PMODE1_44") (pintype "passive"))
    )
    (net (code "53") (name "Net-(U23-PMODE2)") (class "Default")
      (node (ref "RN1") (pin "3") (pintype "passive"))
      (node (ref "U23") (pin "43") (pinfunction "PMODE2_43") (pintype "passive"))
    )
    (net (code "54") (name "Net-(U23-RXN)") (class "Default")
      (node (ref "R61") (pin "2") (pinfunction "2_2") (pintype "passive"))
      (node (ref "U23") (pin "5") (pinfunction "RXN_5") (pintype "passive"))
    )
    (net (code "55") (name "Net-(U23-RXP)") (class "Default")
      (node (ref "R62") (pin "2") (pinfunction "2_2") (pintype "passive"))
      (node (ref "U23") (pin "6") (pinfunction "RXP_6") (pintype "passive"))
    )
    (net (code "56") (name "Net-(U23-TOCAP)") (class "Default")
      (node (ref "C78") (pin "2") (pinfunction "2_2") (pintype "passive"))
      (node (ref "U23") (pin "20") (pinfunction "TOCAP_20") (pintype "passive"))
    )
    (net (code "57") (name "Net-(U23-TXN)") (class "Default")
      (node (ref "R63") (pin "2") (pinfunction "2_2") (pintype "passive"))
      (node (ref "U23") (pin "1") (pinfunction "TXN_1") (pintype "passive"))
    )
    (net (code "58") (name "Net-(U23-TXP)") (class "Default")
      (node (ref "R64") (pin "2") (pinfunction "2_2") (pintype "passive"))
      (node (ref "U23") (pin "2") (pinfunction "TXP_2") (pintype "passive"))
    )
    (net (code "59") (name "Net-(U23-XI{slash}CLKIN)") (class "Default")
      (node (ref "C80") (pin "2") (pinfunction "2_2") (pintype "passive"))
      (node (ref "R70") (pin "1") (pinfunction "1_1") (pintype "passive"))
      (node (ref "U23") (pin "30") (pinfunction "XI/CLKIN_30") (pintype "passive"))
      (node (ref "X3") (pin "1") (pinfunction "OSC1_1") (pintype "passive"))
    )
    (net (code "60") (name "Net-(U23-XO)") (class "Default")
      (node (ref "C85") (pin "2") (pinfunction "2_2") (pintype "passive"))
      (node (ref "R70") (pin "2") (pinfunction "2_2") (pintype "passive"))
      (node (ref "U23") (pin "31") (pinfunction "XO_31") (pintype "passive"))
      (node (ref "X3") (pin "3") (pinfunction "OSC2_3") (pintype "passive"))
    )
    (net (code "61") (name "POE_PWR_N") (class "Default")
      (node (ref "BR1") (pin "3") (pinfunction "AC~_3") (pintype "passive"))
      (node (ref "BR2") (pin "3") (pinfunction "AC~_3") (pintype "passive"))
      (node (ref "C63") (pin "1") (pinfunction "1_1") (pintype "passive"))
      (node (ref "D6") (pin "2") (pinfunction "K_2") (pintype "passive"))
      (node (ref "R45") (pin "1") (pinfunction "1_1") (pintype "passive"))
      (node (ref "R47") (pin "1") (pinfunction "1_1") (pintype "passive"))
      (node (ref "U20") (pin "4") (pinfunction "VSS_4") (pintype "passive"))
    )
    (net (code "62") (name "POE_PWR_P") (class "Default")
      (node (ref "BR1") (pin "1") (pinfunction "AC~_1") (pintype "passive"))
      (node (ref "BR2") (pin "1") (pinfunction "AC~_1") (pintype "passive"))
      (node (ref "C121") (pin "1") (pintype "passive"))
      (node (ref "C63") (pin "2") (pinfunction "2_2") (pintype "passive"))
      (node (ref "C67") (pin "1") (pintype "passive"))
      (node (ref "D6") (pin "1") (pinfunction "K_1") (pintype "passive"))
      (node (ref "R46") (pin "2") (pinfunction "2_2") (pintype "passive"))
      (node (ref "R52") (pin "2") (pinfunction "2_2") (pintype "passive"))
      (node (ref "R54") (pin "2") (pinfunction "2_2") (pintype "passive"))
      (node (ref "U20") (pin "8") (pinfunction "VDD_8") (pintype "passive"))
      (node (ref "U22") (pin "3") (pinfunction "VIN_3") (pintype "passive"))
    )
    (net (code "63") (name "VDD") (class "Default")
      (node (ref "C72") (pin "2") (pinfunction "2_2") (pintype "passive"))
      (node (ref "C73") (pin "2") (pinfunction "2_2") (pintype "passive"))
      (node (ref "FB10") (pin "1") (pinfunction "1_1") (pintype "passive"))
      (node (ref "FB9") (pin "2") (pinfunction "2_2") (pintype "passive"))
      (node (ref "J13") (pin "12") (pinfunction "ANODE_12") (pintype "passive"))
      (node (ref "J13") (pin "14") (pinfunction "ANODE_14") (pintype "passive"))
      (node (ref "R68") (pin "1") (pinfunction "1_1") (pintype "passive"))
      (node (ref "R69") (pin "1") (pinfunction "1_1") (pintype "passive"))
      (node (ref "RN1") (pin "6") (pintype "passive"))
      (node (ref "RN1") (pin "7") (pintype "passive"))
      (node (ref "RN1") (pin "8") (pintype "passive"))
      (node (ref "U23") (pin "28") (pinfunction "VDD_28") (pintype "passive"))
    )
    (net (code "64") (name "VDDA") (class "Default")
      (node (ref "C77") (pin "2") (pinfunction "2_2") (pintype "passive"))
      (node (ref "C79") (pin "2") (pinfunction "2_2") (pintype "passive"))
      (node (ref "C81") (pin "2") (pinfunction "2_2") (pintype "passive"))
      (node (ref "C82") (pin "2") (pinfunction "2_2") (pintype "passive"))
      (node (ref "C83") (pin "2") (pinfunction "2_2") (pintype "passive"))
      (node (ref "C84") (pin "2") (pinfunction "2_2") (pintype "passive"))
      (node (ref "FB10") (pin "2") (pinfunction "2_2") (pintype "passive"))
      (node (ref "R50") (pin "2") (pinfunction "2_2") (pintype "passive"))
      (node (ref "R58") (pin "2") (pinfunction "2_2") (pintype "passive"))
      (node (ref "R59") (pin "2") (pinfunction "2_2") (pintype "passive"))
      (node (ref "U23") (pin "11") (pinfunction "AVDD_11") (pintype "passive"))
      (node (ref "U23") (pin "15") (pinfunction "AVDD_15") (pintype "passive"))
      (node (ref "U23") (pin "17") (pinfunction "AVDD_17") (pintype "passive"))
      (node (ref "U23") (pin "21") (pinfunction "AVDD_21") (pintype "passive"))
      (node (ref "U23") (pin "4") (pinfunction "AVDD_4") (pintype "passive"))
      (node (ref "U23") (pin "8") (pinfunction "AVDD_8") (pintype "passive"))
    )
    (net (code "65") (name "unconnected-(RN1-Pad4)") (class "Default")
      (node (ref "RN1") (pin "4") (pintype "passive+no_connect"))
    )
    (net (code "66") (name "unconnected-(RN1-Pad5)") (class "Default")
      (node (ref "RN1") (pin "5") (pintype "passive+no_connect"))
    )
    (net (code "67") (name "unconnected-(RN2-Pad1)") (class "Default")
      (node (ref "RN2") (pin "1") (pintype "passive+no_connect"))
    )
    (net (code "68") (name "unconnected-(RN2-Pad2)") (class "Default")
      (node (ref "RN2") (pin "2") (pintype "passive+no_connect"))
    )
    (net (code "69") (name "unconnected-(RN2-Pad7)") (class "Default")
      (node (ref "RN2") (pin "7") (pintype "passive+no_connect"))
    )
    (net (code "70") (name "unconnected-(RN2-Pad8)") (class "Default")
      (node (ref "RN2") (pin "8") (pintype "passive+no_connect"))
    )
    (net (code "71") (name "unconnected-(U20-NC-Pad7)") (class "Default")
      (node (ref "U20") (pin "7") (pinfunction "NC_7") (pintype "passive+no_connect"))
    )
    (net (code "72") (name "unconnected-(U23-DNC-Pad7)") (class "Default")
      (node (ref "U23") (pin "7") (pinfunction "DNC_7") (pintype "passive+no_connect"))
    )
    (net (code "73") (name "unconnected-(U23-DUPLED-Pad26)") (class "Default")
      (node (ref "U23") (pin "26") (pinfunction "DUPLED_26") (pintype "passive+no_connect"))
    )
    (net (code "74") (name "unconnected-(U23-NC-Pad12)") (class "Default")
      (node (ref "U23") (pin "12") (pinfunction "NC_12") (pintype "passive+no_connect"))
    )
    (net (code "75") (name "unconnected-(U23-NC-Pad13)") (class "Default")
      (node (ref "U23") (pin "13") (pinfunction "NC_13") (pintype "passive+no_connect"))
    )
    (net (code "76") (name "unconnected-(U23-NC-Pad46)") (class "Default")
      (node (ref "U23") (pin "46") (pinfunction "NC_46") (pintype "passive+no_connect"))
    )
    (net (code "77") (name "unconnected-(U23-NC-Pad47)") (class "Default")
      (node (ref "U23") (pin "47") (pinfunction "NC_47") (pintype "passive+no_connect"))
    )
    (net (code "78") (name "unconnected-(U23-SPDLED-Pad24)") (class "Default")
      (node (ref "U23") (pin "24") (pinfunction "SPDLED_24") (pintype "passive+no_connect"))
    )
    (net (code "79") (name "unconnected-(U23-VBG-Pad18)") (class "Default")
      (node (ref "U23") (pin "18") (pinfunction "VBG_18") (pintype "passive+no_connect"))
    )
  )
)
